# sim-breakout.net
KiCad netlist of a schematic drawn in EAGLE
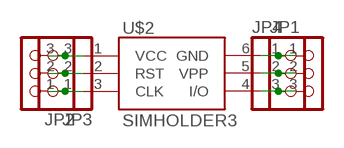
[diagram p0: schematic, sheet 1]

(export (version "E")
  (design (tool "Eeschema 10.0.6"))
  (components
    (comp (ref "JP1")
      (value "PINHD-1X3")
      (footprint "eagle-import:1X03")
      (libsource (lib "eagle-import") (part "PINHD-1X3"))
    )
    (comp (ref "JP2")
      (value "PINHD-1X3")
      (footprint "eagle-import:1X03")
      (libsource (lib "eagle-import") (part "PINHD-1X3"))
    )
    (comp (ref "JP3")
      (value "PINHD-1X3")
      (footprint "eagle-import:1X03")
      (libsource (lib "eagle-import") (part "PINHD-1X3"))
    )
    (comp (ref "JP4")
      (value "PINHD-1X3")
      (footprint "eagle-import:1X03")
      (libsource (lib "eagle-import") (part "PINHD-1X3"))
    )
    (comp (ref "U$2")
      (value "SIMHOLDER3")
      (footprint "eagle-import:SIMHOLDER3")
      (libsource (lib "eagle-import") (part "SIMHOLDER3"))
    )
  )
  (nets
    (net (code "1") (name "Net-(U$2-CLK)") (class "Default")
      (node (ref "JP2") (pin "1") (pinfunction "1_1") (pintype "passive"))
      (node (ref "JP3") (pin "1") (pinfunction "1_1") (pintype "passive"))
      (node (ref "U$2") (pin "3") (pinfunction "CLK_3") (pintype "bidirectional"))
    )
    (net (code "2") (name "Net-(U$2-GND)") (class "Default")
      (node (ref "JP1") (pin "1") (pinfunction "1_1") (pintype "passive"))
      (node (ref "JP4") (pin "1") (pinfunction "1_1") (pintype "passive"))
      (node (ref "U$2") (pin "6") (pinfunction "GND_6") (pintype "bidirectional"))
    )
    (net (code "3") (name "Net-(U$2-I{slash}O)") (class "Default")
      (node (ref "JP1") (pin "3") (pinfunction "3_3") (pintype "passive"))
      (node (ref "JP4") (pin "3") (pinfunction "3_3") (pintype "passive"))
      (node (ref "U$2") (pin "4") (pinfunction "I/O_4") (pintype "bidirectional"))
    )
    (net (code "4") (name "Net-(U$2-RST)") (class "Default")
      (node (ref "JP2") (pin "2") (pinfunction "2_2") (pintype "passive"))
      (node (ref "JP3") (pin "2") (pinfunction "2_2") (pintype "passive"))
      (node (ref "U$2") (pin "2") (pinfunction "RST_2") (pintype "bidirectional"))
    )
    (net (code "5") (name "Net-(U$2-VCC)") (class "Default")
      (node (ref "JP2") (pin "3") (pinfunction "3_3") (pintype "passive"))
      (node (ref "JP3") (pin "3") (pinfunction "3_3") (pintype "passive"))
      (node (ref "U$2") (pin "1") (pinfunction "VCC_1") (pintype "bidirectional"))
    )
    (net (code "6") (name "Net-(U$2-VPP)") (class "Default")
      (node (ref "JP1") (pin "2") (pinfunction "2_2") (pintype "passive"))
      (node (ref "JP4") (pin "2") (pinfunction "2_2") (pintype "passive"))
      (node (ref "U$2") (pin "5") (pinfunction "VPP_5") (pintype "bidirectional"))
    )
  )
)
